# Scematich_PCB.net
KiCad netlist of a schematic drawn in EasyEDA
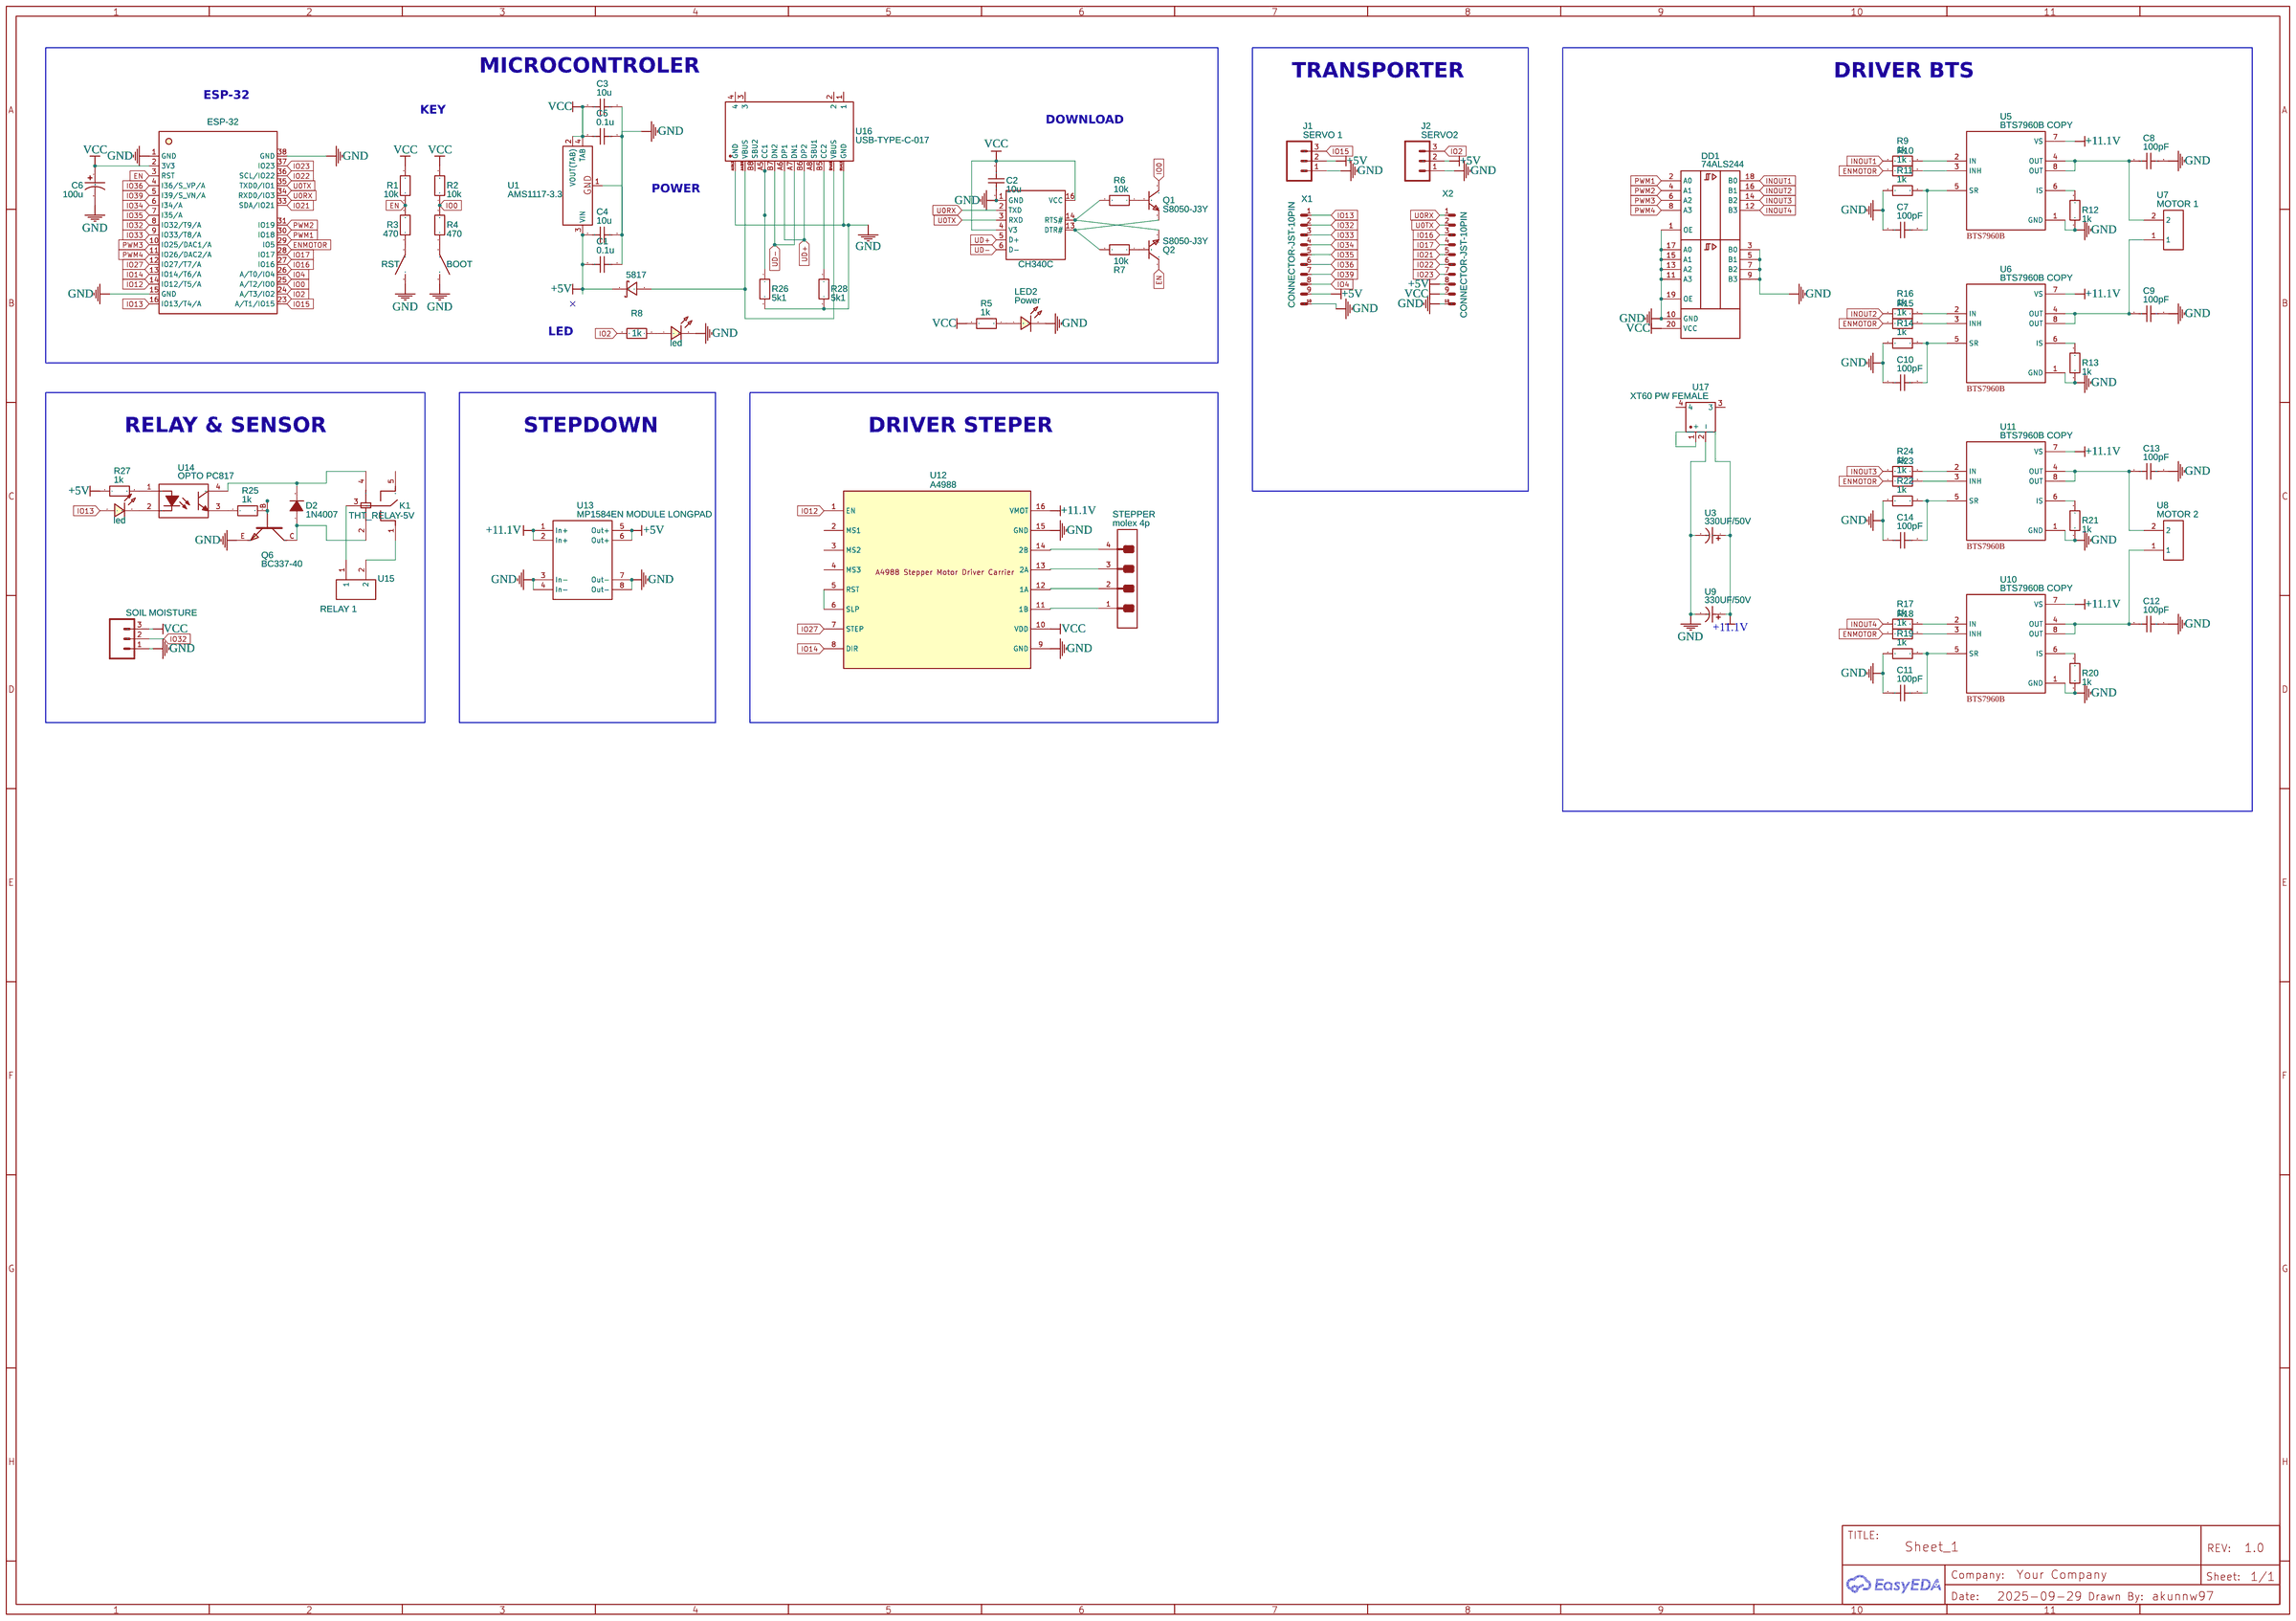
[diagram p0: schematic sheet]

(export (version "E")
  (design (tool "Eeschema 10.0.6"))
  (components
    (comp (ref "C1") (value "0.1u") (libsource (lib "") (part "C_0603_US_2")))
    (comp (ref "C2") (value "10u") (libsource (lib "") (part "C_0603_US")))
    (comp (ref "C3") (value "10u") (libsource (lib "") (part "C_0603_US_2")))
    (comp (ref "C4") (value "10u") (libsource (lib "") (part "C_0603_US_2")))
    (comp (ref "C5") (value "0.1u") (libsource (lib "") (part "C_0603_US_2")))
    (comp (ref "C6") (value "100u") (libsource (lib "") (part "C_Tan_SMD_B_US")))
    (comp (ref "C7") (value "100pF") (libsource (lib "") (part "C_0603_US_1")))
    (comp (ref "C8") (value "100pF") (libsource (lib "") (part "C_0603_US_1")))
    (comp (ref "C9") (value "100pF") (libsource (lib "") (part "C_0603_US_1")))
    (comp (ref "C10") (value "100pF") (libsource (lib "") (part "C_0603_US_1")))
    (comp (ref "C11") (value "100pF") (libsource (lib "") (part "C_0603_US_1")))
    (comp (ref "C12") (value "100pF") (libsource (lib "") (part "C_0603_US_1")))
    (comp (ref "C13") (value "100pF") (libsource (lib "") (part "C_0603_US_1")))
    (comp (ref "C14") (value "100pF") (libsource (lib "") (part "C_0603_US_1")))
    (comp (ref "D1")
      (value "5817")
      (fields
        (field (name "Manufacturer Part") "1N5819W")
        (field (name "Manufacturer") "Shandong Jingdao Microelectronics")
      )
      (libsource (lib "") (part "1N5819W"))
    )
    (comp (ref "D2")
      (value "1N4007")
      (fields (field (name "Manufacturer") "SEMTECH"))
      (libsource (lib "") (part "1N4007"))
    )
    (comp (ref "DD1") (value "74ALS244") (libsource (lib "") (part "74ALS244")))
    (comp (ref "J1") (value "SERVO 1") (libsource (lib "") (part "CONN_03POLAR")))
    (comp (ref "J2") (value "SERVO2") (libsource (lib "") (part "CONN_03POLAR")))
    (comp (ref "J4") (value "SOIL MOISTURE") (libsource (lib "") (part "CONN_03POLAR")))
    (comp (ref "K1")
      (value "THT_RELAY-5V")
      (fields (field (name "Manufacturer Part") "Relay-SPST"))
      (libsource (lib "") (part "THT_RELAY-SPST_5V"))
    )
    (comp (ref "LED1")
      (value "led")
      (fields
        (field (name "Manufacturer Part") "19-217/R6C-AL1M2VY/3T")
        (field (name "Manufacturer") "EVERLIGHT(台湾亿光)")
      )
      (libsource (lib "") (part "LED-0603_R"))
    )
    (comp (ref "LED2")
      (value "Power")
      (fields
        (field (name "Manufacturer Part") "19-217/R6C-AL1M2VY/3T")
        (field (name "Manufacturer") "EVERLIGHT(台湾亿光)")
      )
      (libsource (lib "") (part "LED-0603_R"))
    )
    (comp (ref "LED3")
      (value "led")
      (fields
        (field (name "Manufacturer Part") "19-217/R6C-AL1M2VY/3T")
        (field (name "Manufacturer") "EVERLIGHT(台湾亿光)")
      )
      (libsource (lib "") (part "LED-0603_R"))
    )
    (comp (ref "Q1")
      (value "S8050-J3Y")
      (fields (field (name "Manufacturer") "(MDD) Jiangsu Yutai Elec"))
      (libsource (lib "") (part "S8050-J3Y_1"))
    )
    (comp (ref "Q2")
      (value "S8050-J3Y")
      (fields (field (name "Manufacturer") "(MDD) Jiangsu Yutai Elec"))
      (libsource (lib "") (part "S8050-J3Y"))
    )
    (comp (ref "Q6") (value "BC337-40") (libsource (lib "") (part "BC817-40")))
    (comp (ref "R1") (value "10k") (libsource (lib "") (part "R_0603_EU")))
    (comp (ref "R2") (value "10k") (libsource (lib "") (part "R_0603_EU")))
    (comp (ref "R3") (value "470") (libsource (lib "") (part "R_0603_EU")))
    (comp (ref "R4") (value "470") (libsource (lib "") (part "R_0603_EU")))
    (comp (ref "R5") (value "1k") (libsource (lib "") (part "R_0603_EU_1")))
    (comp (ref "R6") (value "10k") (libsource (lib "") (part "R_0603_EU_1")))
    (comp (ref "R7") (value "10k") (libsource (lib "") (part "R_0603_EU_1")))
    (comp (ref "R8") (value "1k") (libsource (lib "") (part "R_0603_EU_1")))
    (comp (ref "R9") (value "1k") (libsource (lib "") (part "R_0603_EU_2")))
    (comp (ref "R10") (value "1k") (libsource (lib "") (part "R_0603_EU_2")))
    (comp (ref "R11") (value "1k") (libsource (lib "") (part "R_0603_EU_2")))
    (comp (ref "R12") (value "1k") (libsource (lib "") (part "R_0603_EU")))
    (comp (ref "R13") (value "1k") (libsource (lib "") (part "R_0603_EU")))
    (comp (ref "R14") (value "1k") (libsource (lib "") (part "R_0603_EU_2")))
    (comp (ref "R15") (value "1k") (libsource (lib "") (part "R_0603_EU_2")))
    (comp (ref "R16") (value "1k") (libsource (lib "") (part "R_0603_EU_2")))
    (comp (ref "R17") (value "1k") (libsource (lib "") (part "R_0603_EU_2")))
    (comp (ref "R18") (value "1k") (libsource (lib "") (part "R_0603_EU_2")))
    (comp (ref "R19") (value "1k") (libsource (lib "") (part "R_0603_EU_2")))
    (comp (ref "R20") (value "1k") (libsource (lib "") (part "R_0603_EU")))
    (comp (ref "R21") (value "1k") (libsource (lib "") (part "R_0603_EU")))
    (comp (ref "R22") (value "1k") (libsource (lib "") (part "R_0603_EU_2")))
    (comp (ref "R23") (value "1k") (libsource (lib "") (part "R_0603_EU_2")))
    (comp (ref "R24") (value "1k") (libsource (lib "") (part "R_0603_EU_2")))
    (comp (ref "R25") (value "1k") (libsource (lib "") (part "R_0603_EU_2")))
    (comp (ref "R26") (value "5k1") (libsource (lib "") (part "R_0603_EU_3")))
    (comp (ref "R27") (value "1k") (libsource (lib "") (part "R_0603_EU_2")))
    (comp (ref "R28") (value "5k1") (libsource (lib "") (part "R_0603_EU_3")))
    (comp (ref "STEPPER") (value "molex 4p") (libsource (lib "") (part "molex 4p")))
    (comp (ref "SW1")
      (value "RST")
      (fields (field (name "Manufacturer Part") "TSA343G00D-250J2") (field (name "Manufacturer") "BRIGHT"))
      (libsource (lib "") (part "龟仔按键-带柱"))
    )
    (comp (ref "SW2")
      (value "BOOT")
      (fields (field (name "Manufacturer Part") "TSA343G00D-250J2") (field (name "Manufacturer") "BRIGHT"))
      (libsource (lib "") (part "龟仔按键-带柱_1"))
    )
    (comp (ref "U1")
      (value "AMS1117-3.3")
      (fields (field (name "Manufacturer") "Youtai Semiconductor Co., Ltd."))
      (libsource (lib "") (part "AMS1117-3.3"))
    )
    (comp (ref "U2")
      (value "CH340C")
      (fields (field (name "Manufacturer") "WCH"))
      (libsource (lib "") (part "CH340C"))
    )
    (comp (ref "U3") (value "330UF/50V") (libsource (lib "") (part "330UF/50V")))
    (comp (ref "U4")
      (value "ESP-32")
      (fields (field (name "Manufacturer Part") "ESP-32S") (field (name "Manufacturer") "Ai-Thinker"))
      (libsource (lib "") (part "安信可ESP-32S"))
    )
    (comp (ref "U5") (value "BTS7960B COPY") (libsource (lib "") (part "BTS7960B COPY")))
    (comp (ref "U6") (value "BTS7960B COPY") (libsource (lib "") (part "BTS7960B COPY")))
    (comp (ref "U7") (value "MOTOR 1") (libsource (lib "") (part "Terminal block 2p")))
    (comp (ref "U8") (value "MOTOR 2") (libsource (lib "") (part "Terminal block 2p")))
    (comp (ref "U9") (value "330UF/50V") (libsource (lib "") (part "330UF/50V")))
    (comp (ref "U10") (value "BTS7960B COPY") (libsource (lib "") (part "BTS7960B COPY")))
    (comp (ref "U11") (value "BTS7960B COPY") (libsource (lib "") (part "BTS7960B COPY")))
    (comp (ref "U12") (value "A4988") (libsource (lib "") (part "A4988")))
    (comp (ref "U13")
      (value "MP1584EN MODULE LONGPAD")
      (fields (field (name "Manufacturer Part") "MP1584EN Module"))
      (libsource (lib "") (part "MP1584EN MODULE LONGPAD"))
    )
    (comp (ref "U14")
      (value "OPTO PC817")
      (fields (field (name "Manufacturer Part") "PC817B"))
      (libsource (lib "") (part "PC817B"))
    )
    (comp (ref "U15") (value "RELAY 1") (libsource (lib "") (part "Terminal block 2p_1")))
    (comp (ref "U16")
      (value "USB-TYPE-C-017")
      (fields (field (name "Manufacturer") "DEALON(德艺隆)"))
      (libsource (lib "") (part "USB-TYPE-C-017"))
    )
    (comp (ref "U17")
      (value "XT60 PW FEMALE")
      (fields (field (name "Manufacturer") "Amass"))
      (libsource (lib "") (part "XT60 PW FEMALE"))
    )
    (comp (ref "X1")
      (value "CONNECTOR-JST-10PIN")
      (fields (field (name "Manufacturer Part") "B2B-XH-AM(LF)(SN)") (field (name "Manufacturer") "JST"))
      (libsource (lib "") (part "CONNECTOR-JST-10PIN"))
    )
    (comp (ref "X2")
      (value "CONNECTOR-JST-10PIN")
      (fields (field (name "Manufacturer Part") "B2B-XH-AM(LF)(SN)") (field (name "Manufacturer") "JST"))
      (libsource (lib "") (part "CONNECTOR-JST-10PIN_1"))
    )
  )
  (nets
    (net (code "1") (name "+5V") (class "Default")
      (node (ref "C1") (pin "2") (pinfunction "2_2") (pintype "unspecified"))
      (node (ref "C4") (pin "2") (pinfunction "2_2") (pintype "unspecified"))
      (node (ref "D1") (pin "1") (pinfunction "1_1") (pintype "unspecified"))
      (node (ref "J1") (pin "2") (pinfunction "2_2") (pintype "bidirectional"))
      (node (ref "J2") (pin "2") (pinfunction "2_2") (pintype "bidirectional"))
      (node (ref "R27") (pin "1") (pinfunction "1_1") (pintype "unspecified"))
      (node (ref "U1") (pin "3") (pinfunction "VIN_3") (pintype "unspecified"))
      (node (ref "U13") (pin "5") (pinfunction "Out+_5") (pintype "unspecified"))
      (node (ref "U13") (pin "6") (pinfunction "Out+_6") (pintype "unspecified"))
      (node (ref "X1") (pin "9") (pinfunction "9_9") (pintype "unspecified"))
      (node (ref "X2") (pin "8") (pinfunction "8_8") (pintype "unspecified"))
    )
    (net (code "2") (name "+11.1V") (class "Default")
      (node (ref "U10") (pin "7") (pinfunction "VS_7") (pintype "unspecified"))
      (node (ref "U11") (pin "7") (pinfunction "VS_7") (pintype "unspecified"))
      (node (ref "U12") (pin "16") (pinfunction "VMOT_16") (pintype "unspecified"))
      (node (ref "U13") (pin "1") (pinfunction "In+_1") (pintype "unspecified"))
      (node (ref "U13") (pin "2") (pinfunction "In+_2") (pintype "unspecified"))
      (node (ref "U17") (pin "1") (pinfunction "+_1") (pintype "unspecified"))
      (node (ref "U3") (pin "1") (pinfunction "1_1") (pintype "input"))
      (node (ref "U5") (pin "7") (pinfunction "VS_7") (pintype "unspecified"))
      (node (ref "U6") (pin "7") (pinfunction "VS_7") (pintype "unspecified"))
      (node (ref "U9") (pin "1") (pinfunction "1_1") (pintype "input"))
    )
    (net (code "3") (name "EN") (class "Default")
      (node (ref "Q2") (pin "3") (pinfunction "C_3") (pintype "unspecified"))
      (node (ref "R1") (pin "1") (pinfunction "1_1") (pintype "unspecified"))
      (node (ref "R3") (pin "2") (pinfunction "2_2") (pintype "unspecified"))
      (node (ref "U4") (pin "3") (pinfunction "RST_3") (pintype "unspecified"))
    )
    (net (code "4") (name "ENMOTOR") (class "Default")
      (node (ref "R10") (pin "1") (pinfunction "1_1") (pintype "unspecified"))
      (node (ref "R15") (pin "1") (pinfunction "1_1") (pintype "unspecified"))
      (node (ref "R18") (pin "1") (pinfunction "1_1") (pintype "unspecified"))
      (node (ref "R23") (pin "1") (pinfunction "1_1") (pintype "unspecified"))
      (node (ref "U4") (pin "29") (pinfunction "IO5_29") (pintype "unspecified"))
    )
    (net (code "5") (name "GND") (class "Default")
      (node (ref "C1") (pin "1") (pinfunction "1_1") (pintype "unspecified"))
      (node (ref "C10") (pin "1") (pinfunction "1_1") (pintype "unspecified"))
      (node (ref "C11") (pin "1") (pinfunction "1_1") (pintype "unspecified"))
      (node (ref "C12") (pin "2") (pinfunction "2_2") (pintype "unspecified"))
      (node (ref "C13") (pin "2") (pinfunction "2_2") (pintype "unspecified"))
      (node (ref "C14") (pin "1") (pinfunction "1_1") (pintype "unspecified"))
      (node (ref "C2") (pin "1") (pinfunction "1_1") (pintype "unspecified"))
      (node (ref "C3") (pin "1") (pinfunction "1_1") (pintype "unspecified"))
      (node (ref "C4") (pin "1") (pinfunction "1_1") (pintype "unspecified"))
      (node (ref "C5") (pin "1") (pinfunction "1_1") (pintype "unspecified"))
      (node (ref "C6") (pin "2") (pinfunction "2_2") (pintype "unspecified"))
      (node (ref "C7") (pin "1") (pinfunction "1_1") (pintype "unspecified"))
      (node (ref "C8") (pin "2") (pinfunction "2_2") (pintype "unspecified"))
      (node (ref "C9") (pin "2") (pinfunction "2_2") (pintype "unspecified"))
      (node (ref "DD1") (pin "1") (pinfunction "OE_1") (pintype "unspecified"))
      (node (ref "DD1") (pin "10") (pinfunction "GND_10") (pintype "unspecified"))
      (node (ref "DD1") (pin "11") (pinfunction "A3_11") (pintype "unspecified"))
      (node (ref "DD1") (pin "13") (pinfunction "A2_13") (pintype "unspecified"))
      (node (ref "DD1") (pin "15") (pinfunction "A1_15") (pintype "unspecified"))
      (node (ref "DD1") (pin "17") (pinfunction "A0_17") (pintype "unspecified"))
      (node (ref "DD1") (pin "19") (pinfunction "OE_19") (pintype "unspecified"))
      (node (ref "DD1") (pin "3") (pinfunction "B0_3") (pintype "unspecified"))
      (node (ref "DD1") (pin "5") (pinfunction "B1_5") (pintype "unspecified"))
      (node (ref "DD1") (pin "7") (pinfunction "B2_7") (pintype "unspecified"))
      (node (ref "DD1") (pin "9") (pinfunction "B3_9") (pintype "unspecified"))
      (node (ref "J1") (pin "1") (pinfunction "1_1") (pintype "bidirectional"))
      (node (ref "J2") (pin "1") (pinfunction "1_1") (pintype "bidirectional"))
      (node (ref "J4") (pin "1") (pinfunction "1_1") (pintype "bidirectional"))
      (node (ref "LED1") (pin "2") (pinfunction "2_2") (pintype "unspecified"))
      (node (ref "LED2") (pin "2") (pinfunction "2_2") (pintype "unspecified"))
      (node (ref "Q6") (pin "E") (pinfunction "E_E") (pintype "unspecified"))
      (node (ref "R11") (pin "1") (pinfunction "1_1") (pintype "unspecified"))
      (node (ref "R12") (pin "1") (pinfunction "1_1") (pintype "unspecified"))
      (node (ref "R13") (pin "1") (pinfunction "1_1") (pintype "unspecified"))
      (node (ref "R14") (pin "1") (pinfunction "1_1") (pintype "unspecified"))
      (node (ref "R19") (pin "1") (pinfunction "1_1") (pintype "unspecified"))
      (node (ref "R20") (pin "1") (pinfunction "1_1") (pintype "unspecified"))
      (node (ref "R21") (pin "1") (pinfunction "1_1") (pintype "unspecified"))
      (node (ref "R22") (pin "1") (pinfunction "1_1") (pintype "unspecified"))
      (node (ref "R26") (pin "2") (pinfunction "2_2") (pintype "unspecified"))
      (node (ref "R28") (pin "2") (pinfunction "2_2") (pintype "unspecified"))
      (node (ref "SW1") (pin "2") (pinfunction "2_2") (pintype "input"))
      (node (ref "SW2") (pin "2") (pinfunction "2_2") (pintype "input"))
      (node (ref "U1") (pin "1") (pinfunction "ADJ(GND)_1") (pintype "unspecified"))
      (node (ref "U10") (pin "1") (pinfunction "GND_1") (pintype "unspecified"))
      (node (ref "U11") (pin "1") (pinfunction "GND_1") (pintype "unspecified"))
      (node (ref "U12") (pin "15") (pinfunction "GND_15") (pintype "unspecified"))
      (node (ref "U12") (pin "9") (pinfunction "GND_9") (pintype "unspecified"))
      (node (ref "U13") (pin "3") (pinfunction "In-_3") (pintype "unspecified"))
      (node (ref "U13") (pin "4") (pinfunction "In-_4") (pintype "unspecified"))
      (node (ref "U13") (pin "7") (pinfunction "Out-_7") (pintype "unspecified"))
      (node (ref "U13") (pin "8") (pinfunction "Out-_8") (pintype "unspecified"))
      (node (ref "U16") (pin "A1B12") (pinfunction "GND_A1B12") (pintype "unspecified"))
      (node (ref "U16") (pin "B1A12") (pinfunction "GND_B1A12") (pintype "unspecified"))
      (node (ref "U17") (pin "2") (pinfunction "-_2") (pintype "unspecified"))
      (node (ref "U2") (pin "1") (pinfunction "GND_1") (pintype "unspecified"))
      (node (ref "U3") (pin "2") (pinfunction "2_2") (pintype "input"))
      (node (ref "U4") (pin "1") (pinfunction "GND_1") (pintype "unspecified"))
      (node (ref "U4") (pin "15") (pinfunction "GND_15") (pintype "unspecified"))
      (node (ref "U4") (pin "38") (pinfunction "GND_38") (pintype "unspecified"))
      (node (ref "U5") (pin "1") (pinfunction "GND_1") (pintype "unspecified"))
      (node (ref "U6") (pin "1") (pinfunction "GND_1") (pintype "unspecified"))
      (node (ref "U9") (pin "2") (pinfunction "2_2") (pintype "input"))
      (node (ref "X1") (pin "10") (pinfunction "10_10") (pintype "unspecified"))
      (node (ref "X2") (pin "10") (pinfunction "10_10") (pintype "unspecified"))
    )
    (net (code "6") (name "INOUT1") (class "Default")
      (node (ref "DD1") (pin "18") (pinfunction "B0_18") (pintype "unspecified"))
      (node (ref "R9") (pin "1") (pinfunction "1_1") (pintype "unspecified"))
    )
    (net (code "7") (name "INOUT2") (class "Default")
      (node (ref "DD1") (pin "16") (pinfunction "B1_16") (pintype "unspecified"))
      (node (ref "R16") (pin "1") (pinfunction "1_1") (pintype "unspecified"))
    )
    (net (code "8") (name "INOUT3") (class "Default")
      (node (ref "DD1") (pin "14") (pinfunction "B2_14") (pintype "unspecified"))
      (node (ref "R24") (pin "1") (pinfunction "1_1") (pintype "unspecified"))
    )
    (net (code "9") (name "INOUT4") (class "Default")
      (node (ref "DD1") (pin "12") (pinfunction "B3_12") (pintype "unspecified"))
      (node (ref "R17") (pin "1") (pinfunction "1_1") (pintype "unspecified"))
    )
    (net (code "10") (name "IO0") (class "Default")
      (node (ref "Q1") (pin "3") (pinfunction "C_3") (pintype "unspecified"))
      (node (ref "R2") (pin "1") (pinfunction "1_1") (pintype "unspecified"))
      (node (ref "R4") (pin "2") (pinfunction "2_2") (pintype "unspecified"))
      (node (ref "U4") (pin "25") (pinfunction "A/T2/IO0_25") (pintype "unspecified"))
    )
    (net (code "11") (name "IO2") (class "Default")
      (node (ref "J2") (pin "3") (pinfunction "3_3") (pintype "bidirectional"))
      (node (ref "R8") (pin "2") (pinfunction "2_2") (pintype "unspecified"))
      (node (ref "U4") (pin "24") (pinfunction "A/T3/IO2_24") (pintype "unspecified"))
    )
    (net (code "12") (name "IO4") (class "Default")
      (node (ref "U4") (pin "26") (pinfunction "A/T0/IO4_26") (pintype "unspecified"))
      (node (ref "X1") (pin "8") (pinfunction "8_8") (pintype "unspecified"))
    )
    (net (code "13") (name "IO12") (class "Default")
      (node (ref "U12") (pin "1") (pinfunction "EN_1") (pintype "unspecified"))
      (node (ref "U4") (pin "14") (pinfunction "IO12/T5/A_14") (pintype "unspecified"))
    )
    (net (code "14") (name "IO13") (class "Default")
      (node (ref "LED3") (pin "1") (pinfunction "1_1") (pintype "unspecified"))
      (node (ref "U4") (pin "16") (pinfunction "IO13/T4/A_16") (pintype "unspecified"))
      (node (ref "X1") (pin "1") (pinfunction "1_1") (pintype "unspecified"))
    )
    (net (code "15") (name "IO14") (class "Default")
      (node (ref "U12") (pin "8") (pinfunction "DIR_8") (pintype "unspecified"))
      (node (ref "U4") (pin "13") (pinfunction "IO14/T6/A_13") (pintype "unspecified"))
    )
    (net (code "16") (name "IO15") (class "Default")
      (node (ref "J1") (pin "3") (pinfunction "3_3") (pintype "bidirectional"))
      (node (ref "U4") (pin "23") (pinfunction "A/T1/IO15_23") (pintype "unspecified"))
    )
    (net (code "17") (name "IO16") (class "Default")
      (node (ref "U4") (pin "27") (pinfunction "IO16_27") (pintype "unspecified"))
      (node (ref "X2") (pin "3") (pinfunction "3_3") (pintype "unspecified"))
    )
    (net (code "18") (name "IO17") (class "Default")
      (node (ref "U4") (pin "28") (pinfunction "IO17_28") (pintype "unspecified"))
      (node (ref "X2") (pin "4") (pinfunction "4_4") (pintype "unspecified"))
    )
    (net (code "19") (name "IO21") (class "Default")
      (node (ref "U4") (pin "33") (pinfunction "SDA/IO21_33") (pintype "unspecified"))
      (node (ref "X2") (pin "5") (pinfunction "5_5") (pintype "unspecified"))
    )
    (net (code "20") (name "IO22") (class "Default")
      (node (ref "U4") (pin "36") (pinfunction "SCL/IO22_36") (pintype "unspecified"))
      (node (ref "X2") (pin "6") (pinfunction "6_6") (pintype "unspecified"))
    )
    (net (code "21") (name "IO23") (class "Default")
      (node (ref "U4") (pin "37") (pinfunction "IO23_37") (pintype "unspecified"))
      (node (ref "X2") (pin "7") (pinfunction "7_7") (pintype "unspecified"))
    )
    (net (code "22") (name "IO27") (class "Default")
      (node (ref "U12") (pin "7") (pinfunction "STEP_7") (pintype "unspecified"))
      (node (ref "U4") (pin "12") (pinfunction "IO27/T7/A_12") (pintype "unspecified"))
    )
    (net (code "23") (name "IO32") (class "Default")
      (node (ref "J4") (pin "2") (pinfunction "2_2") (pintype "bidirectional"))
      (node (ref "U4") (pin "8") (pinfunction "IO32/T9/A_8") (pintype "unspecified"))
      (node (ref "X1") (pin "2") (pinfunction "2_2") (pintype "unspecified"))
    )
    (net (code "24") (name "IO33") (class "Default")
      (node (ref "U4") (pin "9") (pinfunction "IO33/T8/A_9") (pintype "unspecified"))
      (node (ref "X1") (pin "3") (pinfunction "3_3") (pintype "unspecified"))
    )
    (net (code "25") (name "IO34") (class "Default")
      (node (ref "U4") (pin "6") (pinfunction "I34/A_6") (pintype "unspecified"))
      (node (ref "X1") (pin "4") (pinfunction "4_4") (pintype "unspecified"))
    )
    (net (code "26") (name "IO35") (class "Default")
      (node (ref "U4") (pin "7") (pinfunction "I35/A_7") (pintype "unspecified"))
      (node (ref "X1") (pin "5") (pinfunction "5_5") (pintype "unspecified"))
    )
    (net (code "27") (name "IO36") (class "Default")
      (node (ref "U4") (pin "4") (pinfunction "I36/S_VP/A_4") (pintype "unspecified"))
      (node (ref "X1") (pin "6") (pinfunction "6_6") (pintype "unspecified"))
    )
    (net (code "28") (name "IO39") (class "Default")
      (node (ref "U4") (pin "5") (pinfunction "I39/S_VN/A_5") (pintype "unspecified"))
      (node (ref "X1") (pin "7") (pinfunction "7_7") (pintype "unspecified"))
    )
    (net (code "29") (name "Net-(C8-Pad1)") (class "Default")
      (node (ref "C8") (pin "1") (pinfunction "1_1") (pintype "unspecified"))
      (node (ref "U5") (pin "4") (pinfunction "OUT_4") (pintype "unspecified"))
      (node (ref "U5") (pin "8") (pinfunction "OUT_8") (pintype "unspecified"))
      (node (ref "U7") (pin "2") (pinfunction "2_2") (pintype "unspecified"))
    )
    (net (code "30") (name "Net-(C9-Pad1)") (class "Default")
      (node (ref "C9") (pin "1") (pinfunction "1_1") (pintype "unspecified"))
      (node (ref "U6") (pin "4") (pinfunction "OUT_4") (pintype "unspecified"))
      (node (ref "U6") (pin "8") (pinfunction "OUT_8") (pintype "unspecified"))
      (node (ref "U7") (pin "1") (pinfunction "1_1") (pintype "unspecified"))
    )
    (net (code "31") (name "Net-(C12-Pad1)") (class "Default")
      (node (ref "C12") (pin "1") (pinfunction "1_1") (pintype "unspecified"))
      (node (ref "U10") (pin "4") (pinfunction "OUT_4") (pintype "unspecified"))
      (node (ref "U10") (pin "8") (pinfunction "OUT_8") (pintype "unspecified"))
      (node (ref "U8") (pin "1") (pinfunction "1_1") (pintype "unspecified"))
    )
    (net (code "32") (name "Net-(C13-Pad1)") (class "Default")
      (node (ref "C13") (pin "1") (pinfunction "1_1") (pintype "unspecified"))
      (node (ref "U11") (pin "4") (pinfunction "OUT_4") (pintype "unspecified"))
      (node (ref "U11") (pin "8") (pinfunction "OUT_8") (pintype "unspecified"))
      (node (ref "U8") (pin "2") (pinfunction "2_2") (pintype "unspecified"))
    )
    (net (code "33") (name "Net-(D1-Pad2)") (class "Default")
      (node (ref "D1") (pin "2") (pinfunction "2_2") (pintype "unspecified"))
      (node (ref "U16") (pin "A4B9") (pinfunction "VBUS_A4B9") (pintype "unspecified"))
      (node (ref "U16") (pin "B4A9") (pinfunction "VBUS_B4A9") (pintype "unspecified"))
    )
    (net (code "34") (name "Net-(D2-A)") (class "Default")
      (node (ref "D2") (pin "1") (pinfunction "A_1") (pintype "unspecified"))
      (node (ref "K1") (pin "2") (pinfunction "2_2") (pintype "unspecified"))
      (node (ref "Q6") (pin "C") (pinfunction "C_C") (pintype "unspecified"))
    )
    (net (code "35") (name "Net-(D2-K)") (class "Default")
      (node (ref "D2") (pin "2") (pinfunction "K_2") (pintype "unspecified"))
      (node (ref "K1") (pin "4") (pinfunction "4_4") (pintype "unspecified"))
      (node (ref "U14") (pin "4") (pinfunction "COL_4") (pintype "unspecified"))
    )
    (net (code "36") (name "Net-(K1-Pad1)") (class "Default")
      (node (ref "K1") (pin "1") (pinfunction "1_1") (pintype "unspecified"))
      (node (ref "U15") (pin "2") (pinfunction "2_2") (pintype "unspecified"))
    )
    (net (code "37") (name "Net-(K1-Pad3)") (class "Default")
      (node (ref "K1") (pin "3") (pinfunction "3_3") (pintype "unspecified"))
      (node (ref "U15") (pin "1") (pinfunction "1_1") (pintype "unspecified"))
    )
    (net (code "38") (name "Net-(LED1-Pad1)") (class "Default")
      (node (ref "LED1") (pin "1") (pinfunction "1_1") (pintype "unspecified"))
      (node (ref "R8") (pin "1") (pinfunction "1_1") (pintype "unspecified"))
    )
    (net (code "39") (name "Net-(LED2-Pad1)") (class "Default")
      (node (ref "LED2") (pin "1") (pinfunction "1_1") (pintype "unspecified"))
      (node (ref "R5") (pin "1") (pinfunction "1_1") (pintype "unspecified"))
    )
    (net (code "40") (name "Net-(Q1-B)") (class "Default")
      (node (ref "Q1") (pin "1") (pinfunction "B_1") (pintype "unspecified"))
      (node (ref "R6") (pin "1") (pinfunction "1_1") (pintype "unspecified"))
    )
    (net (code "41") (name "Net-(Q1-E)") (class "Default")
      (node (ref "Q1") (pin "2") (pinfunction "E_2") (pintype "unspecified"))
      (node (ref "R7") (pin "2") (pinfunction "2_2") (pintype "unspecified"))
      (node (ref "U2") (pin "13") (pinfunction "DTR#_13") (pintype "unspecified"))
    )
    (net (code "42") (name "Net-(Q2-B)") (class "Default")
      (node (ref "Q2") (pin "1") (pinfunction "B_1") (pintype "unspecified"))
      (node (ref "R7") (pin "1") (pinfunction "1_1") (pintype "unspecified"))
    )
    (net (code "43") (name "Net-(Q2-E)") (class "Default")
      (node (ref "Q2") (pin "2") (pinfunction "E_2") (pintype "unspecified"))
      (node (ref "R6") (pin "2") (pinfunction "2_2") (pintype "unspecified"))
      (node (ref "U2") (pin "14") (pinfunction "RTS#_14") (pintype "unspecified"))
    )
    (net (code "44") (name "Net-(Q6-PadB)") (class "Default")
      (node (ref "Q6") (pin "B") (pinfunction "B_B") (pintype "unspecified"))
      (node (ref "R25") (pin "2") (pinfunction "2_2") (pintype "unspecified"))
    )
    (net (code "45") (name "Net-(R3-Pad1)") (class "Default")
      (node (ref "R3") (pin "1") (pinfunction "1_1") (pintype "unspecified"))
      (node (ref "SW1") (pin "1") (pinfunction "1_1") (pintype "input"))
    )
    (net (code "46") (name "Net-(R4-Pad1)") (class "Default")
      (node (ref "R4") (pin "1") (pinfunction "1_1") (pintype "unspecified"))
      (node (ref "SW2") (pin "1") (pinfunction "1_1") (pintype "input"))
    )
    (net (code "47") (name "Net-(U5-IN)") (class "Default")
      (node (ref "R9") (pin "2") (pinfunction "2_2") (pintype "unspecified"))
      (node (ref "U5") (pin "2") (pinfunction "IN_2") (pintype "unspecified"))
    )
    (net (code "48") (name "Net-(U5-INH)") (class "Default")
      (node (ref "R10") (pin "2") (pinfunction "2_2") (pintype "unspecified"))
      (node (ref "U5") (pin "3") (pinfunction "INH_3") (pintype "unspecified"))
    )
    (net (code "49") (name "Net-(U5-IS)") (class "Default")
      (node (ref "R12") (pin "2") (pinfunction "2_2") (pintype "unspecified"))
      (node (ref "U5") (pin "6") (pinfunction "IS_6") (pintype "unspecified"))
    )
    (net (code "50") (name "Net-(U5-SR)") (class "Default")
      (node (ref "C7") (pin "2") (pinfunction "2_2") (pintype "unspecified"))
      (node (ref "R11") (pin "2") (pinfunction "2_2") (pintype "unspecified"))
      (node (ref "U5") (pin "5") (pinfunction "SR_5") (pintype "unspecified"))
    )
    (net (code "51") (name "Net-(U6-IN)") (class "Default")
      (node (ref "R16") (pin "2") (pinfunction "2_2") (pintype "unspecified"))
      (node (ref "U6") (pin "2") (pinfunction "IN_2") (pintype "unspecified"))
    )
    (net (code "52") (name "Net-(U6-INH)") (class "Default")
      (node (ref "R15") (pin "2") (pinfunction "2_2") (pintype "unspecified"))
      (node (ref "U6") (pin "3") (pinfunction "INH_3") (pintype "unspecified"))
    )
    (net (code "53") (name "Net-(U6-IS)") (class "Default")
      (node (ref "R13") (pin "2") (pinfunction "2_2") (pintype "unspecified"))
      (node (ref "U6") (pin "6") (pinfunction "IS_6") (pintype "unspecified"))
    )
    (net (code "54") (name "Net-(U6-SR)") (class "Default")
      (node (ref "C10") (pin "2") (pinfunction "2_2") (pintype "unspecified"))
      (node (ref "R14") (pin "2") (pinfunction "2_2") (pintype "unspecified"))
      (node (ref "U6") (pin "5") (pinfunction "SR_5") (pintype "unspecified"))
    )
    (net (code "55") (name "Net-(U10-IN)") (class "Default")
      (node (ref "R17") (pin "2") (pinfunction "2_2") (pintype "unspecified"))
      (node (ref "U10") (pin "2") (pinfunction "IN_2") (pintype "unspecified"))
    )
    (net (code "56") (name "Net-(U10-INH)") (class "Default")
      (node (ref "R18") (pin "2") (pinfunction "2_2") (pintype "unspecified"))
      (node (ref "U10") (pin "3") (pinfunction "INH_3") (pintype "unspecified"))
    )
    (net (code "57") (name "Net-(U10-IS)") (class "Default")
      (node (ref "R20") (pin "2") (pinfunction "2_2") (pintype "unspecified"))
      (node (ref "U10") (pin "6") (pinfunction "IS_6") (pintype "unspecified"))
    )
    (net (code "58") (name "Net-(U10-SR)") (class "Default")
      (node (ref "C11") (pin "2") (pinfunction "2_2") (pintype "unspecified"))
      (node (ref "R19") (pin "2") (pinfunction "2_2") (pintype "unspecified"))
      (node (ref "U10") (pin "5") (pinfunction "SR_5") (pintype "unspecified"))
    )
    (net (code "59") (name "Net-(U11-IN)") (class "Default")
      (node (ref "R24") (pin "2") (pinfunction "2_2") (pintype "unspecified"))
      (node (ref "U11") (pin "2") (pinfunction "IN_2") (pintype "unspecified"))
    )
    (net (code "60") (name "Net-(U11-INH)") (class "Default")
      (node (ref "R23") (pin "2") (pinfunction "2_2") (pintype "unspecified"))
      (node (ref "U11") (pin "3") (pinfunction "INH_3") (pintype "unspecified"))
    )
    (net (code "61") (name "Net-(U11-IS)") (class "Default")
      (node (ref "R21") (pin "2") (pinfunction "2_2") (pintype "unspecified"))
      (node (ref "U11") (pin "6") (pinfunction "IS_6") (pintype "unspecified"))
    )
    (net (code "62") (name "Net-(U11-SR)") (class "Default")
      (node (ref "C14") (pin "2") (pinfunction "2_2") (pintype "unspecified"))
      (node (ref "R22") (pin "2") (pinfunction "2_2") (pintype "unspecified"))
      (node (ref "U11") (pin "5") (pinfunction "SR_5") (pintype "unspecified"))
    )
    (net (code "63") (name "Net-(U12-1A)") (class "Default")
      (node (ref "STEPPER") (pin "2") (pinfunction "2_2") (pintype "bidirectional"))
      (node (ref "U12") (pin "12") (pinfunction "1A_12") (pintype "unspecified"))
    )
    (net (code "64") (name "Net-(U12-1B)") (class "Default")
      (node (ref "STEPPER") (pin "1") (pinfunction "1_1") (pintype "bidirectional"))
      (node (ref "U12") (pin "11") (pinfunction "1B_11") (pintype "unspecified"))
    )
    (net (code "65") (name "Net-(U12-2A)") (class "Default")
      (node (ref "STEPPER") (pin "3") (pinfunction "3_3") (pintype "bidirectional"))
      (node (ref "U12") (pin "13") (pinfunction "2A_13") (pintype "unspecified"))
    )
    (net (code "66") (name "Net-(U12-2B)") (class "Default")
      (node (ref "STEPPER") (pin "4") (pinfunction "4_4") (pintype "bidirectional"))
      (node (ref "U12") (pin "14") (pinfunction "2B_14") (pintype "unspecified"))
    )
    (net (code "67") (name "Net-(U12-RST)") (class "Default")
      (node (ref "U12") (pin "5") (pinfunction "RST_5") (pintype "unspecified"))
      (node (ref "U12") (pin "6") (pinfunction "SLP_6") (pintype "unspecified"))
    )
    (net (code "68") (name "Net-(U14-AN)") (class "Default")
      (node (ref "R27") (pin "2") (pinfunction "2_2") (pintype "unspecified"))
      (node (ref "U14") (pin "1") (pinfunction "AN_1") (pintype "unspecified"))
    )
    (net (code "69") (name "Net-(U14-CAT)") (class "Default")
      (node (ref "LED3") (pin "2") (pinfunction "2_2") (pintype "unspecified"))
      (node (ref "U14") (pin "2") (pinfunction "CAT_2") (pintype "unspecified"))
    )
    (net (code "70") (name "Net-(U14-EM)") (class "Default")
      (node (ref "R25") (pin "1") (pinfunction "1_1") (pintype "unspecified"))
      (node (ref "U14") (pin "3") (pinfunction "EM_3") (pintype "unspecified"))
    )
    (net (code "71") (name "Net-(U16-CC1)") (class "Default")
      (node (ref "R26") (pin "1") (pinfunction "1_1") (pintype "unspecified"))
      (node (ref "U16") (pin "A5") (pinfunction "CC1_A5") (pintype "unspecified"))
    )
    (net (code "72") (name "Net-(U16-CC2)") (class "Default")
      (node (ref "R28") (pin "1") (pinfunction "1_1") (pintype "unspecified"))
      (node (ref "U16") (pin "B5") (pinfunction "CC2_B5") (pintype "unspecified"))
    )
    (net (code "73") (name "PWM1") (class "Default")
      (node (ref "DD1") (pin "2") (pinfunction "A0_2") (pintype "unspecified"))
      (node (ref "U4") (pin "30") (pinfunction "IO18_30") (pintype "unspecified"))
    )
    (net (code "74") (name "PWM2") (class "Default")
      (node (ref "DD1") (pin "4") (pinfunction "A1_4") (pintype "unspecified"))
      (node (ref "U4") (pin "31") (pinfunction "IO19_31") (pintype "unspecified"))
    )
    (net (code "75") (name "PWM3") (class "Default")
      (node (ref "DD1") (pin "6") (pinfunction "A2_6") (pintype "unspecified"))
      (node (ref "U4") (pin "10") (pinfunction "IO25/DAC1/A_10") (pintype "unspecified"))
    )
    (net (code "76") (name "PWM4") (class "Default")
      (node (ref "DD1") (pin "8") (pinfunction "A3_8") (pintype "unspecified"))
      (node (ref "U4") (pin "11") (pinfunction "IO26/DAC2/A_11") (pintype "unspecified"))
    )
    (net (code "77") (name "U0RX") (class "Default")
      (node (ref "U2") (pin "2") (pinfunction "TXD_2") (pintype "unspecified"))
      (node (ref "U4") (pin "34") (pinfunction "RXD0/IO3_34") (pintype "unspecified"))
      (node (ref "X2") (pin "1") (pinfunction "1_1") (pintype "unspecified"))
    )
    (net (code "78") (name "U0TX") (class "Default")
      (node (ref "U2") (pin "3") (pinfunction "RXD_3") (pintype "unspecified"))
      (node (ref "U4") (pin "35") (pinfunction "TXD0/IO1_35") (pintype "unspecified"))
      (node (ref "X2") (pin "2") (pinfunction "2_2") (pintype "unspecified"))
    )
    (net (code "79") (name "UD+") (class "Default")
      (node (ref "U16") (pin "A6") (pinfunction "DP1_A6") (pintype "unspecified"))
      (node (ref "U16") (pin "B6") (pinfunction "DP2_B6") (pintype "unspecified"))
      (node (ref "U2") (pin "5") (pinfunction "D+_5") (pintype "unspecified"))
    )
    (net (code "80") (name "UD-") (class "Default")
      (node (ref "U16") (pin "A7") (pinfunction "DN1_A7") (pintype "unspecified"))
      (node (ref "U16") (pin "B7") (pinfunction "DN2_B7") (pintype "unspecified"))
      (node (ref "U2") (pin "6") (pinfunction "D-_6") (pintype "unspecified"))
    )
    (net (code "81") (name "VCC") (class "Default")
      (node (ref "C2") (pin "2") (pinfunction "2_2") (pintype "unspecified"))
      (node (ref "C3") (pin "2") (pinfunction "2_2") (pintype "unspecified"))
      (node (ref "C5") (pin "2") (pinfunction "2_2") (pintype "unspecified"))
      (node (ref "C6") (pin "1") (pinfunction "1_1") (pintype "unspecified"))
      (node (ref "DD1") (pin "20") (pinfunction "VCC_20") (pintype "unspecified"))
      (node (ref "J4") (pin "3") (pinfunction "3_3") (pintype "bidirectional"))
      (node (ref "R1") (pin "2") (pinfunction "2_2") (pintype "unspecified"))
      (node (ref "R2") (pin "2") (pinfunction "2_2") (pintype "unspecified"))
      (node (ref "R5") (pin "2") (pinfunction "2_2") (pintype "unspecified"))
      (node (ref "U1") (pin "2") (pinfunction "VOUT(TAB)_2") (pintype "unspecified"))
      (node (ref "U1") (pin "4") (pinfunction "TAB_4") (pintype "unspecified"))
      (node (ref "U12") (pin "10") (pinfunction "VDD_10") (pintype "unspecified"))
      (node (ref "U2") (pin "16") (pinfunction "VCC_16") (pintype "unspecified"))
      (node (ref "U2") (pin "4") (pinfunction "V3_4") (pintype "unspecified"))
      (node (ref "U4") (pin "2") (pinfunction "3V3_2") (pintype "unspecified"))
      (node (ref "X2") (pin "9") (pinfunction "9_9") (pintype "unspecified"))
    )
    (net (code "82") (name "unconnected-(K1-Pad5)") (class "Default")
      (node (ref "K1") (pin "5") (pinfunction "5_5") (pintype "unspecified"))
    )
    (net (code "83") (name "unconnected-(U12-MS1-Pad2)") (class "Default")
      (node (ref "U12") (pin "2") (pinfunction "MS1_2") (pintype "unspecified"))
    )
    (net (code "84") (name "unconnected-(U12-MS2-Pad3)") (class "Default")
      (node (ref "U12") (pin "3") (pinfunction "MS2_3") (pintype "unspecified"))
    )
    (net (code "85") (name "unconnected-(U12-MS3-Pad4)") (class "Default")
      (node (ref "U12") (pin "4") (pinfunction "MS3_4") (pintype "unspecified"))
    )
    (net (code "86") (name "unconnected-(U16-Pad1)") (class "Default")
      (node (ref "U16") (pin "1") (pinfunction "1_1") (pintype "unspecified"))
    )
    (net (code "87") (name "unconnected-(U16-Pad2)") (class "Default")
      (node (ref "U16") (pin "2") (pinfunction "2_2") (pintype "unspecified"))
    )
    (net (code "88") (name "unconnected-(U16-Pad3)") (class "Default")
      (node (ref "U16") (pin "3") (pinfunction "3_3") (pintype "unspecified"))
    )
    (net (code "89") (name "unconnected-(U16-Pad4)") (class "Default")
      (node (ref "U16") (pin "4") (pinfunction "4_4") (pintype "unspecified"))
    )
    (net (code "90") (name "unconnected-(U16-SBU1-PadA8)") (class "Default")
      (node (ref "U16") (pin "A8") (pinfunction "SBU1_A8") (pintype "unspecified"))
    )
    (net (code "91") (name "unconnected-(U16-SBU2-PadB8)") (class "Default")
      (node (ref "U16") (pin "B8") (pinfunction "SBU2_B8") (pintype "unspecified"))
    )
    (net (code "92") (name "unconnected-(U17-Pad3)") (class "Default")
      (node (ref "U17") (pin "3") (pinfunction "3_3") (pintype "unspecified"))
    )
    (net (code "93") (name "unconnected-(U17-Pad4)") (class "Default")
      (node (ref "U17") (pin "4") (pinfunction "4_4") (pintype "unspecified"))
    )
  )
)
